# SparkFun_Pro_Micro.net
KiCad netlist of a schematic drawn in EAGLE
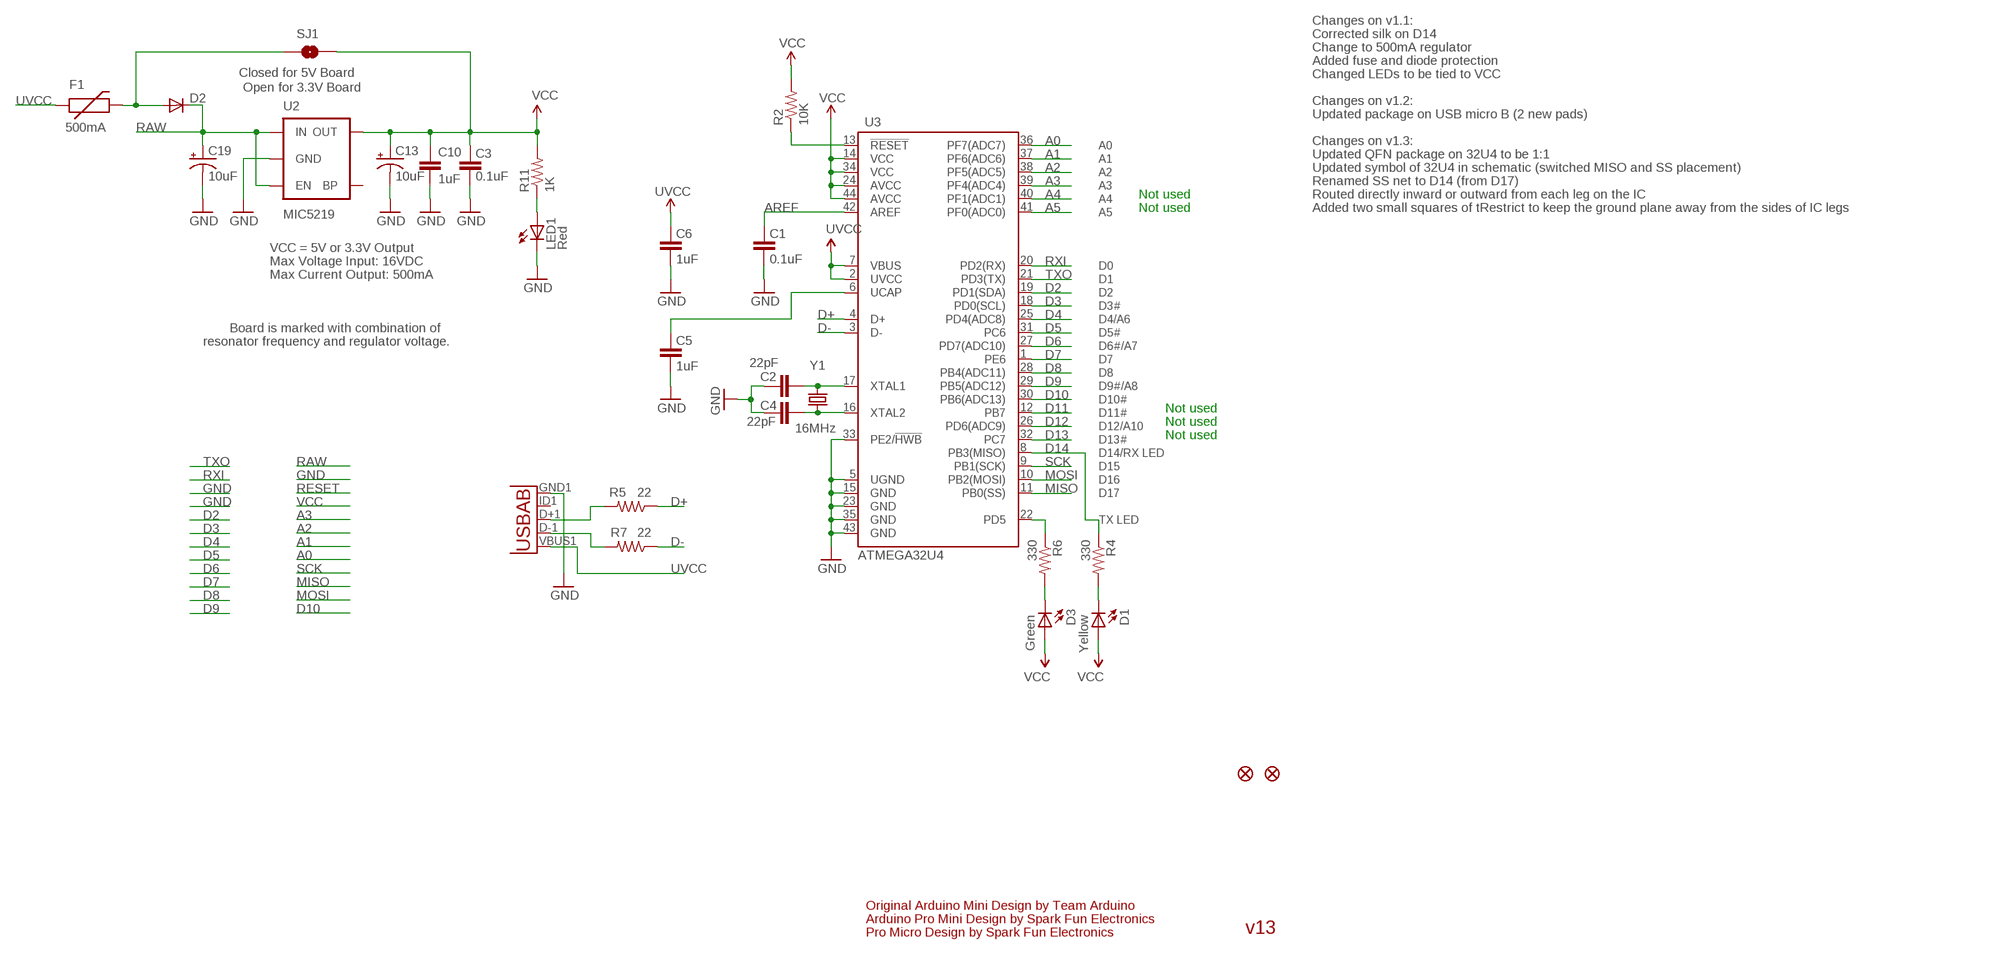
[diagram p0: schematic, sheet 1]

(export (version "E")
  (design (tool "Eeschema 10.0.6"))
  (components
    (comp (ref "C1")
      (value "0.1uF")
      (footprint "eagle-import:0603-CAP")
      (libsource (lib "eagle-import") (part "CAP0603-CAP"))
    )
    (comp (ref "C2")
      (value "22pF")
      (footprint "eagle-import:0603-CAP")
      (libsource (lib "eagle-import") (part "CAP0603-CAP"))
    )
    (comp (ref "C3")
      (value "0.1uF")
      (footprint "eagle-import:0603-CAP")
      (libsource (lib "eagle-import") (part "CAP0603-CAP"))
    )
    (comp (ref "C4")
      (value "22pF")
      (footprint "eagle-import:0603-CAP")
      (libsource (lib "eagle-import") (part "CAP0603-CAP"))
    )
    (comp (ref "C5")
      (value "1uF")
      (footprint "eagle-import:0603-CAP")
      (libsource (lib "eagle-import") (part "CAP0603-CAP"))
    )
    (comp (ref "C6")
      (value "1uF")
      (footprint "eagle-import:0603-CAP")
      (libsource (lib "eagle-import") (part "CAP0603-CAP"))
    )
    (comp (ref "C10")
      (value "1uF")
      (footprint "eagle-import:0603-CAP")
      (libsource (lib "eagle-import") (part "CAP0603-CAP"))
    )
    (comp (ref "C13")
      (value "10uF")
      (footprint "eagle-import:EIA3216")
      (libsource (lib "eagle-import") (part "CAP_POL1206"))
    )
    (comp (ref "C19")
      (value "10uF")
      (footprint "eagle-import:EIA3216")
      (libsource (lib "eagle-import") (part "CAP_POL1206"))
    )
    (comp (ref "D1")
      (value "Yellow")
      (footprint "eagle-import:LED-0603")
      (libsource (lib "eagle-import") (part "LED0603"))
    )
    (comp (ref "D2")
      (value "DIODESOD")
      (footprint "eagle-import:SOD-323")
      (libsource (lib "eagle-import") (part "DIODESOD"))
    )
    (comp (ref "D3")
      (value "Green")
      (footprint "eagle-import:LED-0603")
      (libsource (lib "eagle-import") (part "LED0603"))
    )
    (comp (ref "F1")
      (value "500mA")
      (footprint "eagle-import:PTC-1206")
      (libsource (lib "eagle-import") (part "PTCSMD"))
    )
    (comp (ref "JP1")
      (value "FIDUCIALUFIDUCIAL")
      (footprint "eagle-import:MICRO-FIDUCIAL")
      (libsource (lib "eagle-import") (part "FIDUCIALUFIDUCIAL"))
    )
    (comp (ref "JP2")
      (value "FIDUCIALUFIDUCIAL")
      (footprint "eagle-import:MICRO-FIDUCIAL")
      (libsource (lib "eagle-import") (part "FIDUCIALUFIDUCIAL"))
    )
    (comp (ref "LED1")
      (value "Red")
      (footprint "eagle-import:LED-0603")
      (libsource (lib "eagle-import") (part "LED0603"))
    )
    (comp (ref "R2")
      (value "10K")
      (footprint "eagle-import:0603-RES")
      (libsource (lib "eagle-import") (part "RESISTOR0603-RES"))
    )
    (comp (ref "R4")
      (value "330")
      (footprint "eagle-import:0603-RES")
      (libsource (lib "eagle-import") (part "RESISTOR0603-RES"))
    )
    (comp (ref "R5")
      (value "22")
      (footprint "eagle-import:0603-RES")
      (libsource (lib "eagle-import") (part "RESISTOR0603-RES"))
    )
    (comp (ref "R6")
      (value "330")
      (footprint "eagle-import:0603-RES")
      (libsource (lib "eagle-import") (part "RESISTOR0603-RES"))
    )
    (comp (ref "R7")
      (value "22")
      (footprint "eagle-import:0603-RES")
      (libsource (lib "eagle-import") (part "RESISTOR0603-RES"))
    )
    (comp (ref "R11")
      (value "1K")
      (footprint "eagle-import:0603-RES")
      (libsource (lib "eagle-import") (part "RESISTOR0603-RES"))
    )
    (comp (ref "SJ1")
      (value "Closed for 5V Board")
      (footprint "eagle-import:SJ_2S")
      (libsource (lib "eagle-import") (part "SOLDERJUMPERNC"))
    )
    (comp (ref "U2")
      (value "MIC5219")
      (footprint "eagle-import:SOT23-5")
      (libsource (lib "eagle-import") (part "V_REG_LDOSMD"))
    )
    (comp (ref "U3")
      (value "ATMEGA32U4")
      (footprint "eagle-import:QFN-44-NOPAD_1_1-OUTFAKES")
      (libsource (lib "eagle-import") (part "ATMEGA32U4OUTFAKES"))
    )
    (comp (ref "X1")
      (value "USB-ABIN&OUT")
      (footprint "eagle-import:USB-AB-MICRO-SMD-V03-IN&OUT")
      (libsource (lib "eagle-import") (part "USB-ABIN&OUT"))
    )
    (comp (ref "Y1")
      (value "16MHz")
      (footprint "eagle-import:CRYSTAL-SMD-5X3")
      (libsource (lib "eagle-import") (part "CRYSTAL5X3"))
    )
  )
  (nets
    (net (code "1") (name "/A0") (class "Default")
      (node (ref "U3") (pin "36") (pinfunction "PF7(ADC7)_36") (pintype "bidirectional"))
    )
    (net (code "2") (name "/A1") (class "Default")
      (node (ref "U3") (pin "37") (pinfunction "PF6(ADC6)_37") (pintype "bidirectional"))
    )
    (net (code "3") (name "/A2") (class "Default")
      (node (ref "U3") (pin "38") (pinfunction "PF5(ADC5)_38") (pintype "bidirectional"))
    )
    (net (code "4") (name "/A3") (class "Default")
      (node (ref "U3") (pin "39") (pinfunction "PF4(ADC4)_39") (pintype "bidirectional"))
    )
    (net (code "5") (name "/A4") (class "Default")
      (node (ref "U3") (pin "40") (pinfunction "PF1(ADC1)_40") (pintype "bidirectional"))
    )
    (net (code "6") (name "/A5") (class "Default")
      (node (ref "U3") (pin "41") (pinfunction "PF0(ADC0)_41") (pintype "bidirectional"))
    )
    (net (code "7") (name "/AREF") (class "Default")
      (node (ref "C1") (pin "2") (pinfunction "2_2") (pintype "passive"))
      (node (ref "U3") (pin "42") (pinfunction "AREF_42") (pintype "bidirectional"))
    )
    (net (code "8") (name "/D+") (class "Default")
      (node (ref "R5") (pin "1") (pinfunction "1_1") (pintype "passive"))
      (node (ref "U3") (pin "4") (pinfunction "D+_4") (pintype "bidirectional"))
    )
    (net (code "9") (name "/D-") (class "Default")
      (node (ref "R7") (pin "1") (pinfunction "1_1") (pintype "passive"))
      (node (ref "U3") (pin "3") (pinfunction "D-_3") (pintype "bidirectional"))
    )
    (net (code "10") (name "/D2") (class "Default")
      (node (ref "U3") (pin "19") (pinfunction "PD1(SDA)_19") (pintype "bidirectional"))
    )
    (net (code "11") (name "/D3") (class "Default")
      (node (ref "U3") (pin "18") (pinfunction "PD0(SCL)_18") (pintype "bidirectional"))
    )
    (net (code "12") (name "/D4") (class "Default")
      (node (ref "U3") (pin "25") (pinfunction "PD4(ADC8)_25") (pintype "bidirectional"))
    )
    (net (code "13") (name "/D5") (class "Default")
      (node (ref "U3") (pin "31") (pinfunction "PC6_31") (pintype "bidirectional"))
    )
    (net (code "14") (name "/D6") (class "Default")
      (node (ref "U3") (pin "27") (pinfunction "PD7(ADC10)_27") (pintype "bidirectional"))
    )
    (net (code "15") (name "/D7") (class "Default")
      (node (ref "U3") (pin "1") (pinfunction "PE6_1") (pintype "bidirectional"))
    )
    (net (code "16") (name "/D8") (class "Default")
      (node (ref "U3") (pin "28") (pinfunction "PB4(ADC11)_28") (pintype "bidirectional"))
    )
    (net (code "17") (name "/D9") (class "Default")
      (node (ref "U3") (pin "29") (pinfunction "PB5(ADC12)_29") (pintype "bidirectional"))
    )
    (net (code "18") (name "/D10") (class "Default")
      (node (ref "U3") (pin "30") (pinfunction "PB6(ADC13)_30") (pintype "bidirectional"))
    )
    (net (code "19") (name "/D11") (class "Default")
      (node (ref "U3") (pin "12") (pinfunction "PB7_12") (pintype "bidirectional"))
    )
    (net (code "20") (name "/D12") (class "Default")
      (node (ref "U3") (pin "26") (pinfunction "PD6(ADC9)_26") (pintype "bidirectional"))
    )
    (net (code "21") (name "/D13") (class "Default")
      (node (ref "U3") (pin "32") (pinfunction "PC7_32") (pintype "bidirectional"))
    )
    (net (code "22") (name "/D14") (class "Default")
      (node (ref "R4") (pin "1") (pinfunction "1_1") (pintype "passive"))
      (node (ref "U3") (pin "8") (pinfunction "PB3(MISO)_8") (pintype "bidirectional"))
    )
    (net (code "23") (name "/MISO") (class "Default")
      (node (ref "U3") (pin "11") (pinfunction "PB0(SS)_11") (pintype "bidirectional"))
    )
    (net (code "24") (name "/MOSI") (class "Default")
      (node (ref "U3") (pin "10") (pinfunction "PB2(MOSI)_10") (pintype "bidirectional"))
    )
    (net (code "25") (name "/RAW") (class "Default")
      (node (ref "C19") (pin "A") (pinfunction "+_A") (pintype "passive"))
      (node (ref "D2") (pin "1") (pinfunction "C_1") (pintype "passive"))
      (node (ref "U2") (pin "1") (pinfunction "IN_1") (pintype "input"))
      (node (ref "U2") (pin "3") (pinfunction "EN_3") (pintype "input"))
    )
    (net (code "26") (name "/RESET") (class "Default")
      (node (ref "R2") (pin "1") (pinfunction "1_1") (pintype "passive"))
      (node (ref "U3") (pin "13") (pinfunction "~{RESET}_13") (pintype "bidirectional"))
    )
    (net (code "27") (name "/RXI") (class "Default")
      (node (ref "U3") (pin "20") (pinfunction "PD2(RX)_20") (pintype "bidirectional"))
    )
    (net (code "28") (name "/SCK") (class "Default")
      (node (ref "U3") (pin "9") (pinfunction "PB1(SCK)_9") (pintype "bidirectional"))
    )
    (net (code "29") (name "/TXO") (class "Default")
      (node (ref "U3") (pin "21") (pinfunction "PD3(TX)_21") (pintype "bidirectional"))
    )
    (net (code "30") (name "GND") (class "Default")
      (node (ref "C1") (pin "1") (pinfunction "1_1") (pintype "passive"))
      (node (ref "C10") (pin "2") (pinfunction "2_2") (pintype "passive"))
      (node (ref "C13") (pin "C") (pinfunction "-_C") (pintype "passive"))
      (node (ref "C19") (pin "C") (pinfunction "-_C") (pintype "passive"))
      (node (ref "C2") (pin "2") (pinfunction "2_2") (pintype "passive"))
      (node (ref "C3") (pin "1") (pinfunction "1_1") (pintype "passive"))
      (node (ref "C4") (pin "2") (pinfunction "2_2") (pintype "passive"))
      (node (ref "C5") (pin "1") (pinfunction "1_1") (pintype "passive"))
      (node (ref "C6") (pin "1") (pinfunction "1_1") (pintype "passive"))
      (node (ref "LED1") (pin "C") (pinfunction "C_C") (pintype "passive"))
      (node (ref "U2") (pin "2") (pinfunction "GND_2") (pintype "input"))
      (node (ref "U3") (pin "15") (pinfunction "GND_15") (pintype "bidirectional"))
      (node (ref "U3") (pin "23") (pinfunction "GND_23") (pintype "bidirectional"))
      (node (ref "U3") (pin "33") (pinfunction "PE2/~{HWB}_33") (pintype "bidirectional"))
      (node (ref "U3") (pin "35") (pinfunction "GND_35") (pintype "bidirectional"))
      (node (ref "U3") (pin "43") (pinfunction "GND_43") (pintype "bidirectional"))
      (node (ref "U3") (pin "5") (pinfunction "UGND_5") (pintype "bidirectional"))
      (node (ref "X1") (pin "GND1") (pinfunction "GND_GND1") (pintype "bidirectional"))
    )
    (net (code "31") (name "Net-(D1-PadC)") (class "Default")
      (node (ref "D1") (pin "C") (pinfunction "C_C") (pintype "passive"))
      (node (ref "R4") (pin "2") (pinfunction "2_2") (pintype "passive"))
    )
    (net (code "32") (name "Net-(D2-A)") (class "Default")
      (node (ref "D2") (pin "2") (pinfunction "A_2") (pintype "passive"))
      (node (ref "F1") (pin "2") (pinfunction "2_2") (pintype "bidirectional"))
      (node (ref "SJ1") (pin "1") (pinfunction "1_1") (pintype "passive"))
    )
    (net (code "33") (name "Net-(D3-PadC)") (class "Default")
      (node (ref "D3") (pin "C") (pinfunction "C_C") (pintype "passive"))
      (node (ref "R6") (pin "2") (pinfunction "2_2") (pintype "passive"))
    )
    (net (code "34") (name "Net-(LED1-PadA)") (class "Default")
      (node (ref "LED1") (pin "A") (pinfunction "A_A") (pintype "passive"))
      (node (ref "R11") (pin "1") (pinfunction "1_1") (pintype "passive"))
    )
    (net (code "35") (name "Net-(U3-PD5)") (class "Default")
      (node (ref "R6") (pin "1") (pinfunction "1_1") (pintype "passive"))
      (node (ref "U3") (pin "22") (pinfunction "PD5_22") (pintype "bidirectional"))
    )
    (net (code "36") (name "Net-(U3-UCAP)") (class "Default")
      (node (ref "C5") (pin "2") (pinfunction "2_2") (pintype "passive"))
      (node (ref "U3") (pin "6") (pinfunction "UCAP_6") (pintype "bidirectional"))
    )
    (net (code "37") (name "Net-(U3-XTAL1)") (class "Default")
      (node (ref "C2") (pin "1") (pinfunction "1_1") (pintype "passive"))
      (node (ref "U3") (pin "17") (pinfunction "XTAL1_17") (pintype "bidirectional"))
      (node (ref "Y1") (pin "3") (pinfunction "2_3") (pintype "passive"))
    )
    (net (code "38") (name "Net-(U3-XTAL2)") (class "Default")
      (node (ref "C4") (pin "1") (pinfunction "1_1") (pintype "passive"))
      (node (ref "U3") (pin "16") (pinfunction "XTAL2_16") (pintype "bidirectional"))
      (node (ref "Y1") (pin "1") (pinfunction "1_1") (pintype "passive"))
    )
    (net (code "39") (name "Net-(X1-D+)") (class "Default")
      (node (ref "R5") (pin "2") (pinfunction "2_2") (pintype "passive"))
      (node (ref "X1") (pin "D+1") (pinfunction "D+_D+1") (pintype "bidirectional"))
    )
    (net (code "40") (name "Net-(X1-D-)") (class "Default")
      (node (ref "R7") (pin "2") (pinfunction "2_2") (pintype "passive"))
      (node (ref "X1") (pin "D-1") (pinfunction "D-_D-1") (pintype "bidirectional"))
    )
    (net (code "41") (name "UVCC") (class "Default")
      (node (ref "C6") (pin "2") (pinfunction "2_2") (pintype "passive"))
      (node (ref "F1") (pin "1") (pinfunction "1_1") (pintype "bidirectional"))
      (node (ref "U3") (pin "2") (pinfunction "UVCC_2") (pintype "bidirectional"))
      (node (ref "U3") (pin "7") (pinfunction "VBUS_7") (pintype "bidirectional"))
      (node (ref "X1") (pin "VBUS1") (pinfunction "VBUS_VBUS1") (pintype "bidirectional"))
    )
    (net (code "42") (name "VCC") (class "Default")
      (node (ref "C10") (pin "1") (pinfunction "1_1") (pintype "passive"))
      (node (ref "C13") (pin "A") (pinfunction "+_A") (pintype "passive"))
      (node (ref "C3") (pin "2") (pinfunction "2_2") (pintype "passive"))
      (node (ref "D1") (pin "A") (pinfunction "A_A") (pintype "passive"))
      (node (ref "D3") (pin "A") (pinfunction "A_A") (pintype "passive"))
      (node (ref "R11") (pin "2") (pinfunction "2_2") (pintype "passive"))
      (node (ref "R2") (pin "2") (pinfunction "2_2") (pintype "passive"))
      (node (ref "SJ1") (pin "2") (pinfunction "2_2") (pintype "passive"))
      (node (ref "U2") (pin "5") (pinfunction "OUT_5") (pintype "passive"))
      (node (ref "U3") (pin "14") (pinfunction "VCC_14") (pintype "bidirectional"))
      (node (ref "U3") (pin "24") (pinfunction "AVCC_24") (pintype "bidirectional"))
      (node (ref "U3") (pin "34") (pinfunction "VCC_34") (pintype "bidirectional"))
      (node (ref "U3") (pin "44") (pinfunction "AVCC_44") (pintype "bidirectional"))
    )
    (net (code "43") (name "unconnected-(U2-BP-Pad4)") (class "Default")
      (node (ref "U2") (pin "4") (pinfunction "BP_4") (pintype "input"))
    )
    (net (code "44") (name "unconnected-(X1-USBID-PadID1)") (class "Default")
      (node (ref "X1") (pin "ID1") (pinfunction "USBID_ID1") (pintype "bidirectional"))
    )
  )
)
